# esp8266.net
KiCad netlist of a schematic drawn in EAGLE
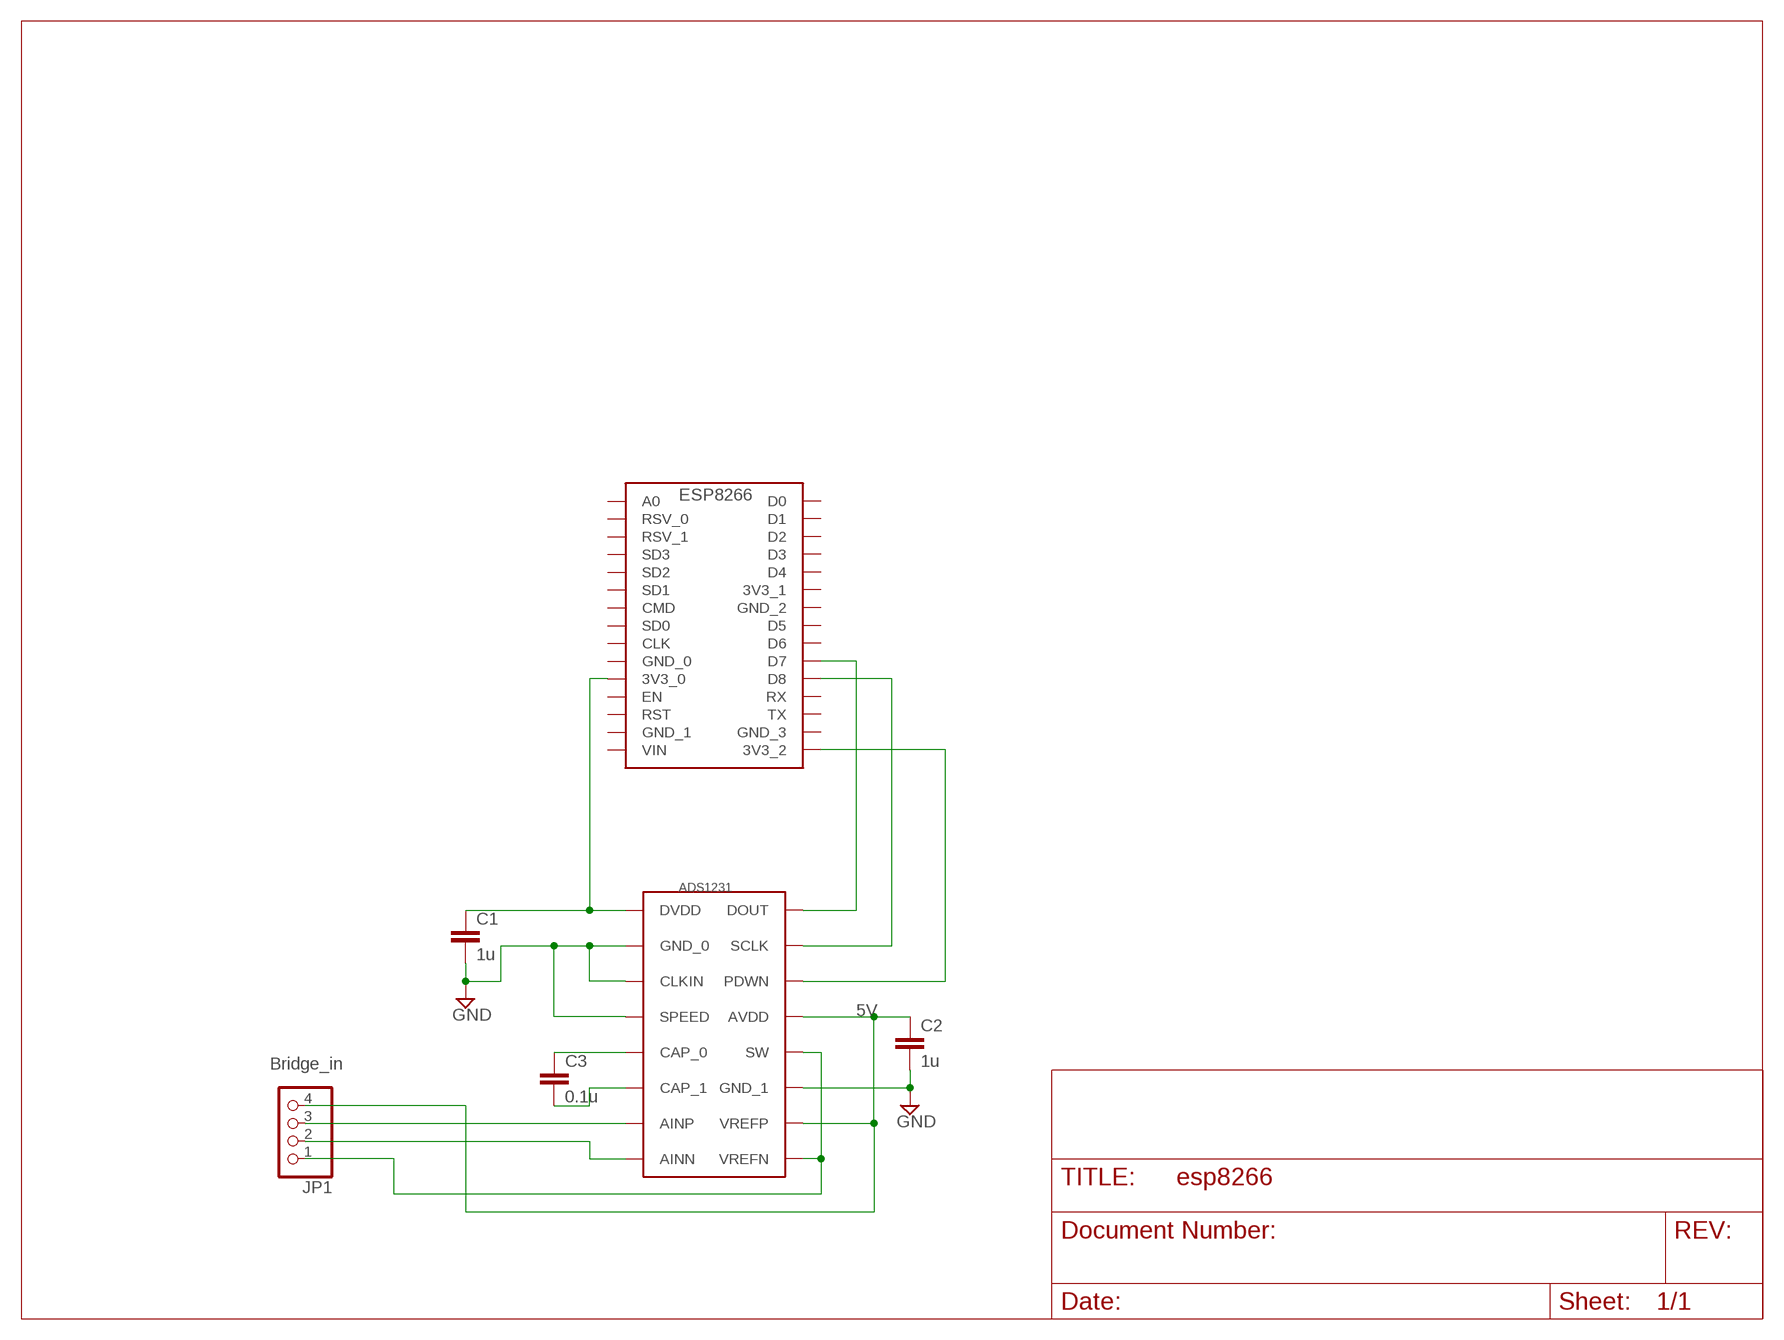
[diagram p0: schematic, sheet 1]

(export (version "E")
  (design (tool "Eeschema 10.0.6"))
  (components
    (comp (ref "ADS1231")
      (value "ADS1231")
      (footprint "eagle-import:ADS1231")
      (libsource (lib "eagle-import") (part "ADS1231"))
    )
    (comp (ref "C1")
      (value "1u")
      (footprint "eagle-import:C0805")
      (libsource (lib "eagle-import") (part "resistor_C-EUC0805"))
    )
    (comp (ref "C2")
      (value "1u")
      (footprint "eagle-import:C0805")
      (libsource (lib "eagle-import") (part "resistor_C-EUC0805"))
    )
    (comp (ref "C3")
      (value "0.1u")
      (footprint "eagle-import:C0805")
      (libsource (lib "eagle-import") (part "C-EUC0805"))
    )
    (comp (ref "ESP8266")
      (value "ESP8266_DEV_NODEMCU_AMICA")
      (footprint "eagle-import:ESP_266_DEV")
      (libsource (lib "eagle-import") (part "ESP8266_DEV_NODEMCU_AMICA"))
    )
    (comp (ref "JP1")
      (value "PINHD-1X4")
      (footprint "eagle-import:1X04")
      (libsource (lib "eagle-import") (part "PINHD-1X4"))
    )
  )
  (nets
    (net (code "1") (name "/5V") (class "Default")
      (node (ref "ADS1231") (pin "AVDD") (pinfunction "AVDD_AVDD") (pintype "bidirectional"))
      (node (ref "ADS1231") (pin "VREFP") (pinfunction "VREFP_VREFP") (pintype "bidirectional"))
      (node (ref "C2") (pin "1") (pinfunction "1_1") (pintype "passive"))
      (node (ref "JP1") (pin "4") (pinfunction "4_4") (pintype "passive"))
    )
    (net (code "2") (name "GND") (class "Default")
      (node (ref "ADS1231") (pin "CLKIN") (pinfunction "CLKIN_CLKIN") (pintype "bidirectional"))
      (node (ref "ADS1231") (pin "GND_0") (pinfunction "GND_0_GND_0") (pintype "bidirectional"))
      (node (ref "ADS1231") (pin "GND_1") (pinfunction "GND_1_GND_1") (pintype "bidirectional"))
      (node (ref "ADS1231") (pin "SPEED") (pinfunction "SPEED_SPEED") (pintype "bidirectional"))
      (node (ref "C1") (pin "2") (pinfunction "2_2") (pintype "passive"))
      (node (ref "C2") (pin "2") (pinfunction "2_2") (pintype "passive"))
    )
    (net (code "3") (name "Net-(ADS1231-PadAINN)") (class "Default")
      (node (ref "ADS1231") (pin "AINN") (pinfunction "AINN_AINN") (pintype "bidirectional"))
      (node (ref "JP1") (pin "2") (pinfunction "2_2") (pintype "passive"))
    )
    (net (code "4") (name "Net-(ADS1231-PadAINP)") (class "Default")
      (node (ref "ADS1231") (pin "AINP") (pinfunction "AINP_AINP") (pintype "bidirectional"))
      (node (ref "JP1") (pin "3") (pinfunction "3_3") (pintype "passive"))
    )
    (net (code "5") (name "Net-(ADS1231-PadCAP_0)") (class "Default")
      (node (ref "ADS1231") (pin "CAP_0") (pinfunction "CAP_0_CAP_0") (pintype "bidirectional"))
      (node (ref "C3") (pin "1") (pinfunction "1_1") (pintype "passive"))
    )
    (net (code "6") (name "Net-(ADS1231-PadCAP_1)") (class "Default")
      (node (ref "ADS1231") (pin "CAP_1") (pinfunction "CAP_1_CAP_1") (pintype "bidirectional"))
      (node (ref "C3") (pin "2") (pinfunction "2_2") (pintype "passive"))
    )
    (net (code "7") (name "Net-(ADS1231-PadDOUT)") (class "Default")
      (node (ref "ADS1231") (pin "DOUT") (pinfunction "DOUT_DOUT") (pintype "bidirectional"))
      (node (ref "ESP8266") (pin "D7") (pinfunction "D7_D7") (pintype "bidirectional"))
    )
    (net (code "8") (name "Net-(ADS1231-PadDVDD)") (class "Default")
      (node (ref "ADS1231") (pin "DVDD") (pinfunction "DVDD_DVDD") (pintype "bidirectional"))
      (node (ref "C1") (pin "1") (pinfunction "1_1") (pintype "passive"))
      (node (ref "ESP8266") (pin "3V3_0") (pinfunction "3V3_0_3V3_0") (pintype "bidirectional"))
    )
    (net (code "9") (name "Net-(ADS1231-PadPDWN)") (class "Default")
      (node (ref "ADS1231") (pin "PDWN") (pinfunction "PDWN_PDWN") (pintype "bidirectional"))
      (node (ref "ESP8266") (pin "3V3_2") (pinfunction "3V3_2_3V3_2") (pintype "bidirectional"))
    )
    (net (code "10") (name "Net-(ADS1231-PadSCLK)") (class "Default")
      (node (ref "ADS1231") (pin "SCLK") (pinfunction "SCLK_SCLK") (pintype "bidirectional"))
      (node (ref "ESP8266") (pin "D8") (pinfunction "D8_D8") (pintype "bidirectional"))
    )
    (net (code "11") (name "Net-(ADS1231-PadSW)") (class "Default")
      (node (ref "ADS1231") (pin "SW") (pinfunction "SW_SW") (pintype "bidirectional"))
      (node (ref "ADS1231") (pin "VREFN") (pinfunction "VREFN_VREFN") (pintype "bidirectional"))
      (node (ref "JP1") (pin "1") (pinfunction "1_1") (pintype "passive"))
    )
    (net (code "12") (name "unconnected-(ESP8266-Pad3V3_1)") (class "Default")
      (node (ref "ESP8266") (pin "3V3_1") (pinfunction "3V3_1_3V3_1") (pintype "bidirectional"))
    )
    (net (code "13") (name "unconnected-(ESP8266-PadA0)") (class "Default")
      (node (ref "ESP8266") (pin "A0") (pinfunction "A0_A0") (pintype "bidirectional"))
    )
    (net (code "14") (name "unconnected-(ESP8266-PadCLK)") (class "Default")
      (node (ref "ESP8266") (pin "CLK") (pinfunction "CLK_CLK") (pintype "bidirectional"))
    )
    (net (code "15") (name "unconnected-(ESP8266-PadCMD)") (class "Default")
      (node (ref "ESP8266") (pin "CMD") (pinfunction "CMD_CMD") (pintype "bidirectional"))
    )
    (net (code "16") (name "unconnected-(ESP8266-PadD0)") (class "Default")
      (node (ref "ESP8266") (pin "D0") (pinfunction "D0_D0") (pintype "bidirectional"))
    )
    (net (code "17") (name "unconnected-(ESP8266-PadD1)") (class "Default")
      (node (ref "ESP8266") (pin "D1") (pinfunction "D1_D1") (pintype "bidirectional"))
    )
    (net (code "18") (name "unconnected-(ESP8266-PadD2)") (class "Default")
      (node (ref "ESP8266") (pin "D2") (pinfunction "D2_D2") (pintype "bidirectional"))
    )
    (net (code "19") (name "unconnected-(ESP8266-PadD3)") (class "Default")
      (node (ref "ESP8266") (pin "D3") (pinfunction "D3_D3") (pintype "bidirectional"))
    )
    (net (code "20") (name "unconnected-(ESP8266-PadD4)") (class "Default")
      (node (ref "ESP8266") (pin "D4") (pinfunction "D4_D4") (pintype "bidirectional"))
    )
    (net (code "21") (name "unconnected-(ESP8266-PadD5)") (class "Default")
      (node (ref "ESP8266") (pin "D5") (pinfunction "D5_D5") (pintype "bidirectional"))
    )
    (net (code "22") (name "unconnected-(ESP8266-PadD6)") (class "Default")
      (node (ref "ESP8266") (pin "D6") (pinfunction "D6_D6") (pintype "bidirectional"))
    )
    (net (code "23") (name "unconnected-(ESP8266-PadEN)") (class "Default")
      (node (ref "ESP8266") (pin "EN") (pinfunction "EN_EN") (pintype "bidirectional"))
    )
    (net (code "24") (name "unconnected-(ESP8266-PadGND_0)") (class "Default")
      (node (ref "ESP8266") (pin "GND_0") (pinfunction "GND_0_GND_0") (pintype "bidirectional"))
    )
    (net (code "25") (name "unconnected-(ESP8266-PadGND_1)") (class "Default")
      (node (ref "ESP8266") (pin "GND_1") (pinfunction "GND_1_GND_1") (pintype "bidirectional"))
    )
    (net (code "26") (name "unconnected-(ESP8266-PadGND_2)") (class "Default")
      (node (ref "ESP8266") (pin "GND_2") (pinfunction "GND_2_GND_2") (pintype "bidirectional"))
    )
    (net (code "27") (name "unconnected-(ESP8266-PadGND_3)") (class "Default")
      (node (ref "ESP8266") (pin "GND_3") (pinfunction "GND_3_GND_3") (pintype "bidirectional"))
    )
    (net (code "28") (name "unconnected-(ESP8266-PadRST)") (class "Default")
      (node (ref "ESP8266") (pin "RST") (pinfunction "RST_RST") (pintype "bidirectional"))
    )
    (net (code "29") (name "unconnected-(ESP8266-PadRSV_0)") (class "Default")
      (node (ref "ESP8266") (pin "RSV_0") (pinfunction "RSV_0_RSV_0") (pintype "bidirectional"))
    )
    (net (code "30") (name "unconnected-(ESP8266-PadRSV_1)") (class "Default")
      (node (ref "ESP8266") (pin "RSV_1") (pinfunction "RSV_1_RSV_1") (pintype "bidirectional"))
    )
    (net (code "31") (name "unconnected-(ESP8266-PadRX)") (class "Default")
      (node (ref "ESP8266") (pin "RX") (pinfunction "RX_RX") (pintype "bidirectional"))
    )
    (net (code "32") (name "unconnected-(ESP8266-PadSD0)") (class "Default")
      (node (ref "ESP8266") (pin "SD0") (pinfunction "SD0_SD0") (pintype "bidirectional"))
    )
    (net (code "33") (name "unconnected-(ESP8266-PadSD1)") (class "Default")
      (node (ref "ESP8266") (pin "SD1") (pinfunction "SD1_SD1") (pintype "bidirectional"))
    )
    (net (code "34") (name "unconnected-(ESP8266-PadSD2)") (class "Default")
      (node (ref "ESP8266") (pin "SD2") (pinfunction "SD2_SD2") (pintype "bidirectional"))
    )
    (net (code "35") (name "unconnected-(ESP8266-PadSD3)") (class "Default")
      (node (ref "ESP8266") (pin "SD3") (pinfunction "SD3_SD3") (pintype "bidirectional"))
    )
    (net (code "36") (name "unconnected-(ESP8266-PadTX)") (class "Default")
      (node (ref "ESP8266") (pin "TX") (pinfunction "TX_TX") (pintype "bidirectional"))
    )
    (net (code "37") (name "unconnected-(ESP8266-PadVIN)") (class "Default")
      (node (ref "ESP8266") (pin "VIN") (pinfunction "VIN_VIN") (pintype "bidirectional"))
    )
  )
)
